# RF_Chip_antenna_example.net
KiCad netlist of a schematic drawn in EAGLE
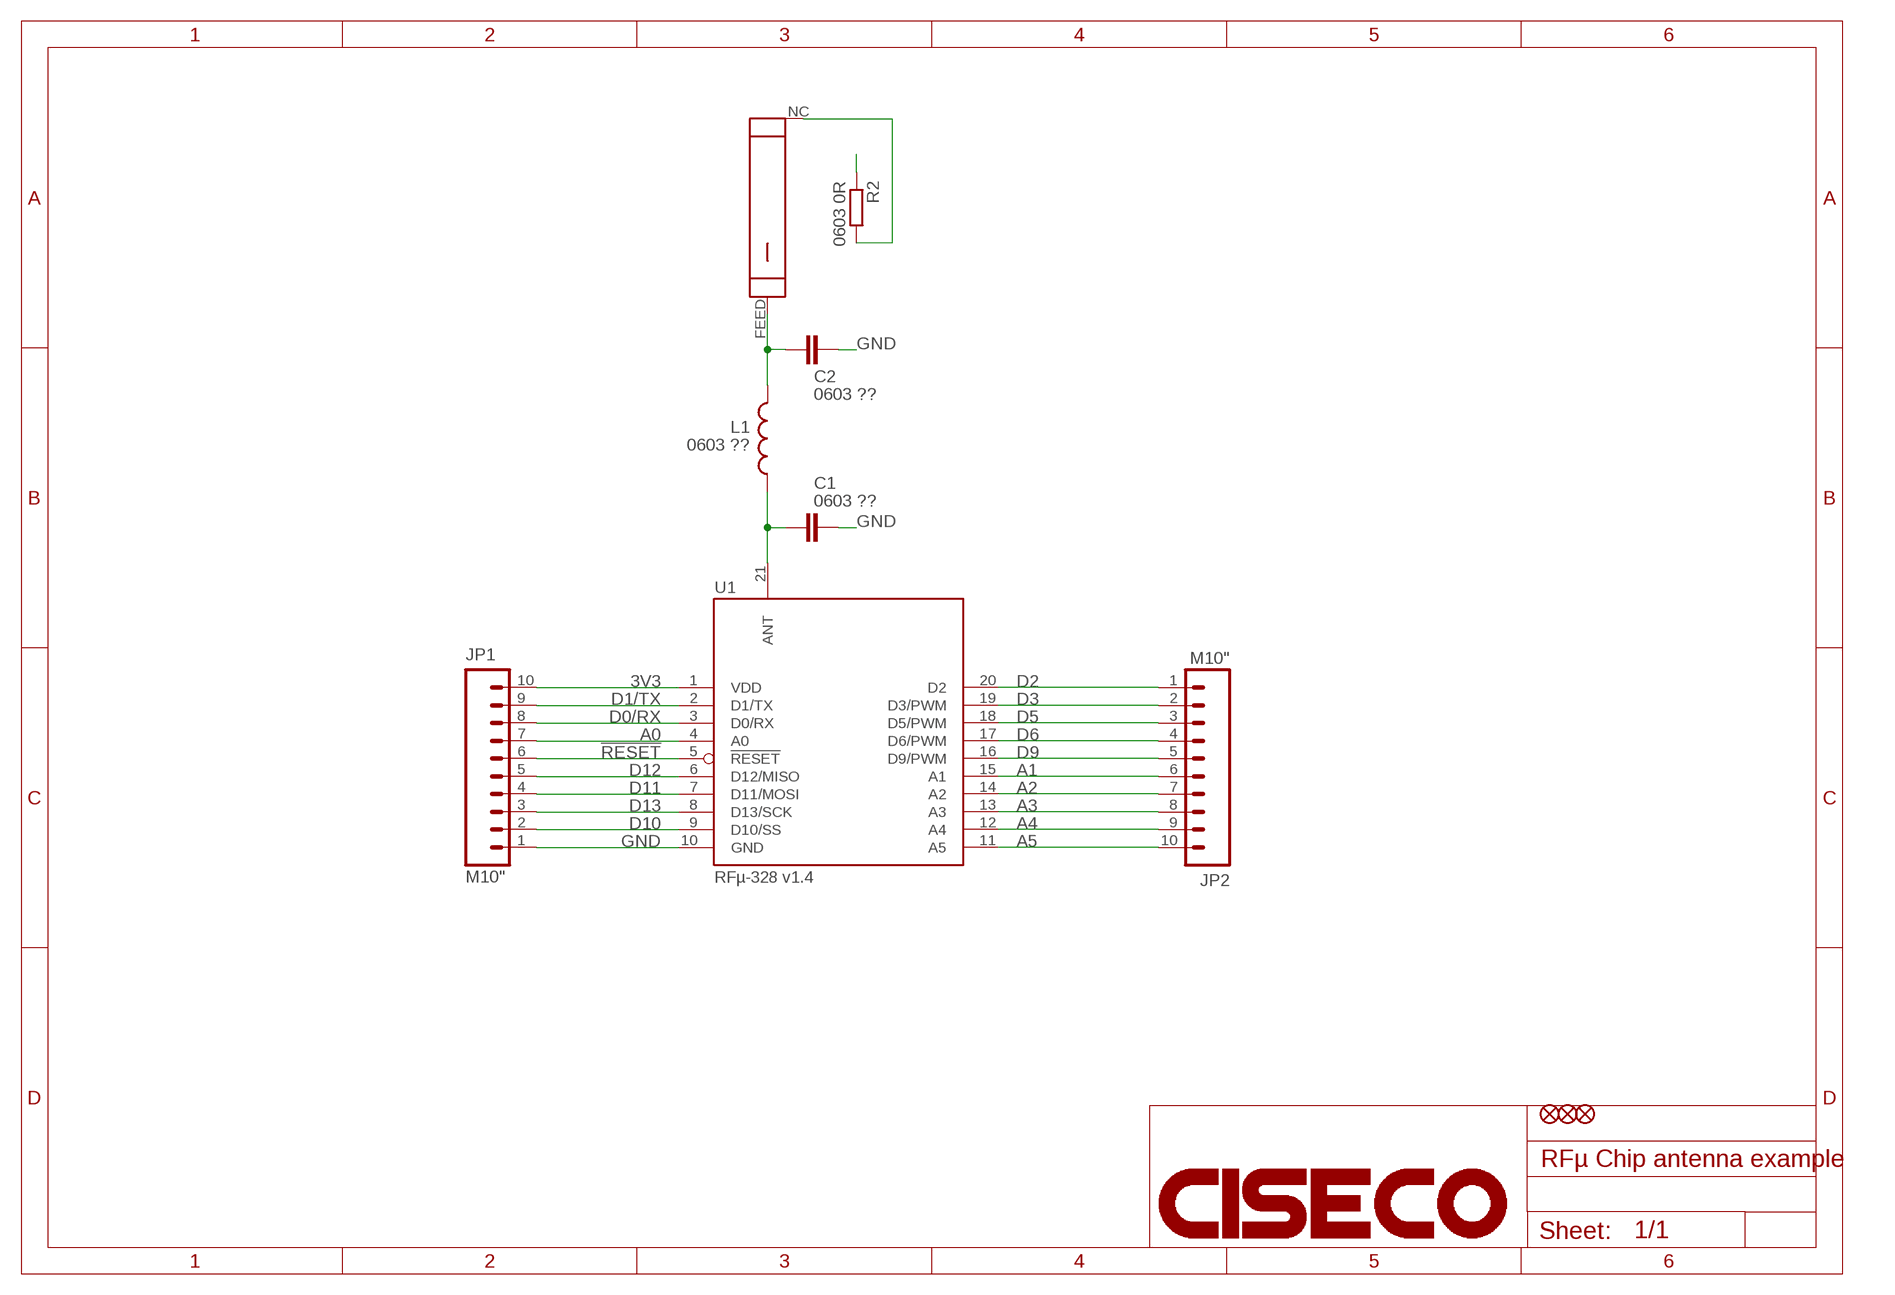
[diagram p0: schematic, sheet 1]

(export (version "E")
  (design (tool "Eeschema 10.0.6"))
  (components
    (comp (ref "C1")
      (value "0603 ??")
      (footprint "eagle-import:C0603K-SMALL")
      (libsource (lib "eagle-import") (part "C-EUC0603K-SMALL"))
    )
    (comp (ref "C2")
      (value "0603 ??")
      (footprint "eagle-import:C0603K-SMALL")
      (libsource (lib "eagle-import") (part "C-EUC0603K-SMALL"))
    )
    (comp (ref "JP1")
      (value "M10\"")
      (footprint "eagle-import:1X10")
      (libsource (lib "eagle-import") (part "M10{dblquote}"))
    )
    (comp (ref "JP2")
      (value "M10\"")
      (footprint "eagle-import:1X10")
      (libsource (lib "eagle-import") (part "M10{dblquote}"))
    )
    (comp (ref "JP3")
      (value "FIDUCIAL1X2.5-STOP")
      (footprint "eagle-import:FIDUCIAL-1X2.5-STOP")
      (libsource (lib "eagle-import") (part "FIDUCIAL1X2.5-STOP"))
    )
    (comp (ref "JP4")
      (value "FIDUCIAL1X2.5-STOP")
      (footprint "eagle-import:FIDUCIAL-1X2.5-STOP")
      (libsource (lib "eagle-import") (part "FIDUCIAL1X2.5-STOP"))
    )
    (comp (ref "JP5")
      (value "FIDUCIAL1X2.5-STOP")
      (footprint "eagle-import:FIDUCIAL-1X2.5-STOP")
      (libsource (lib "eagle-import") (part "FIDUCIAL1X2.5-STOP"))
    )
    (comp (ref "L1")
      (value "0603 ??")
      (footprint "eagle-import:C0603K-SMALL")
      (libsource (lib "eagle-import") (part "INDUCTOR0603K-SMALL"))
    )
    (comp (ref "LOGO1")
      (value "CISECOLOGO-4MM")
      (footprint "eagle-import:CISECO-4MM")
      (libsource (lib "eagle-import") (part "CISECOLOGO-4MM"))
    )
    (comp (ref "R2")
      (value "0603 0R")
      (footprint "eagle-import:C0603K-SMALL")
      (libsource (lib "eagle-import") (part "R-EU_0603K-SMALL"))
    )
    (comp (ref "U$1")
      (value "JTICHIPANT")
      (footprint "eagle-import:JTICHIPANT")
      (libsource (lib "eagle-import") (part "JTICHIPANT"))
    )
    (comp (ref "U1")
      (value "RFµ-328 v1.4")
      (footprint "eagle-import:RFµ-LANDING-V2.0")
      (libsource (lib "eagle-import") (part "RFµ-328-SMD-V2.0"))
    )
  )
  (nets
    (net (code "1") (name "/3V3") (class "Default")
      (node (ref "JP1") (pin "10") (pinfunction "10_10") (pintype "passive"))
      (node (ref "U1") (pin "1") (pinfunction "VDD_1") (pintype "power_in"))
    )
    (net (code "2") (name "/A0") (class "Default")
      (node (ref "JP1") (pin "7") (pinfunction "7_7") (pintype "passive"))
      (node (ref "U1") (pin "4") (pinfunction "A0_4") (pintype "bidirectional"))
    )
    (net (code "3") (name "/A1") (class "Default")
      (node (ref "JP2") (pin "6") (pinfunction "6_6") (pintype "passive"))
      (node (ref "U1") (pin "15") (pinfunction "A1_15") (pintype "bidirectional"))
    )
    (net (code "4") (name "/A2") (class "Default")
      (node (ref "JP2") (pin "7") (pinfunction "7_7") (pintype "passive"))
      (node (ref "U1") (pin "14") (pinfunction "A2_14") (pintype "bidirectional"))
    )
    (net (code "5") (name "/A3") (class "Default")
      (node (ref "JP2") (pin "8") (pinfunction "8_8") (pintype "passive"))
      (node (ref "U1") (pin "13") (pinfunction "A3_13") (pintype "bidirectional"))
    )
    (net (code "6") (name "/A4") (class "Default")
      (node (ref "JP2") (pin "9") (pinfunction "9_9") (pintype "passive"))
      (node (ref "U1") (pin "12") (pinfunction "A4_12") (pintype "output"))
    )
    (net (code "7") (name "/A5") (class "Default")
      (node (ref "JP2") (pin "10") (pinfunction "10_10") (pintype "passive"))
      (node (ref "U1") (pin "11") (pinfunction "A5_11") (pintype "bidirectional"))
    )
    (net (code "8") (name "/D0{slash}RX") (class "Default")
      (node (ref "JP1") (pin "8") (pinfunction "8_8") (pintype "passive"))
      (node (ref "U1") (pin "3") (pinfunction "D0/RX_3") (pintype "input"))
    )
    (net (code "9") (name "/D1{slash}TX") (class "Default")
      (node (ref "JP1") (pin "9") (pinfunction "9_9") (pintype "passive"))
      (node (ref "U1") (pin "2") (pinfunction "D1/TX_2") (pintype "output"))
    )
    (net (code "10") (name "/D2") (class "Default")
      (node (ref "JP2") (pin "1") (pinfunction "1_1") (pintype "passive"))
      (node (ref "U1") (pin "20") (pinfunction "D2_20") (pintype "bidirectional"))
    )
    (net (code "11") (name "/D3") (class "Default")
      (node (ref "JP2") (pin "2") (pinfunction "2_2") (pintype "passive"))
      (node (ref "U1") (pin "19") (pinfunction "D3/PWM_19") (pintype "bidirectional"))
    )
    (net (code "12") (name "/D5") (class "Default")
      (node (ref "JP2") (pin "3") (pinfunction "3_3") (pintype "passive"))
      (node (ref "U1") (pin "18") (pinfunction "D5/PWM_18") (pintype "bidirectional"))
    )
    (net (code "13") (name "/D6") (class "Default")
      (node (ref "JP2") (pin "4") (pinfunction "4_4") (pintype "passive"))
      (node (ref "U1") (pin "17") (pinfunction "D6/PWM_17") (pintype "bidirectional"))
    )
    (net (code "14") (name "/D9") (class "Default")
      (node (ref "JP2") (pin "5") (pinfunction "5_5") (pintype "passive"))
      (node (ref "U1") (pin "16") (pinfunction "D9/PWM_16") (pintype "input"))
    )
    (net (code "15") (name "/D10") (class "Default")
      (node (ref "JP1") (pin "2") (pinfunction "2_2") (pintype "passive"))
      (node (ref "U1") (pin "9") (pinfunction "D10/SS_9") (pintype "bidirectional"))
    )
    (net (code "16") (name "/D11") (class "Default")
      (node (ref "JP1") (pin "4") (pinfunction "4_4") (pintype "passive"))
      (node (ref "U1") (pin "7") (pinfunction "D11/MOSI_7") (pintype "bidirectional"))
    )
    (net (code "17") (name "/D12") (class "Default")
      (node (ref "JP1") (pin "5") (pinfunction "5_5") (pintype "passive"))
      (node (ref "U1") (pin "6") (pinfunction "D12/MISO_6") (pintype "bidirectional"))
    )
    (net (code "18") (name "/D13") (class "Default")
      (node (ref "JP1") (pin "3") (pinfunction "3_3") (pintype "passive"))
      (node (ref "U1") (pin "8") (pinfunction "D13/SCK_8") (pintype "bidirectional"))
    )
    (net (code "19") (name "/GND") (class "Default")
      (node (ref "C1") (pin "2") (pinfunction "2_2") (pintype "passive"))
      (node (ref "C2") (pin "2") (pinfunction "2_2") (pintype "passive"))
      (node (ref "JP1") (pin "1") (pinfunction "1_1") (pintype "passive"))
      (node (ref "U1") (pin "10") (pinfunction "GND_10") (pintype "power_in"))
    )
    (net (code "20") (name "/~{RESET}") (class "Default")
      (node (ref "JP1") (pin "6") (pinfunction "6_6") (pintype "passive"))
      (node (ref "U1") (pin "5") (pinfunction "~{RESET}_5") (pintype "input"))
    )
    (net (code "21") (name "Net-(U$1-P$1)") (class "Default")
      (node (ref "R2") (pin "2") (pinfunction "2_2") (pintype "passive"))
      (node (ref "U$1") (pin "NC") (pinfunction "P$1_NC") (pintype "bidirectional"))
    )
    (net (code "22") (name "Net-(U$1-P$2)") (class "Default")
      (node (ref "C2") (pin "1") (pinfunction "1_1") (pintype "passive"))
      (node (ref "L1") (pin "2") (pinfunction "2_2") (pintype "passive"))
      (node (ref "U$1") (pin "FEED") (pinfunction "P$2_FEED") (pintype "bidirectional"))
    )
    (net (code "23") (name "Net-(U1-ANT)") (class "Default")
      (node (ref "C1") (pin "1") (pinfunction "1_1") (pintype "passive"))
      (node (ref "L1") (pin "1") (pinfunction "1_1") (pintype "passive"))
      (node (ref "U1") (pin "21") (pinfunction "ANT_21") (pintype "output"))
    )
    (net (code "24") (name "unconnected-(R2-Pad1)") (class "Default")
      (node (ref "R2") (pin "1") (pinfunction "1_1") (pintype "passive"))
    )
  )
)
